# shield.net
KiCad netlist of a schematic drawn in EAGLE
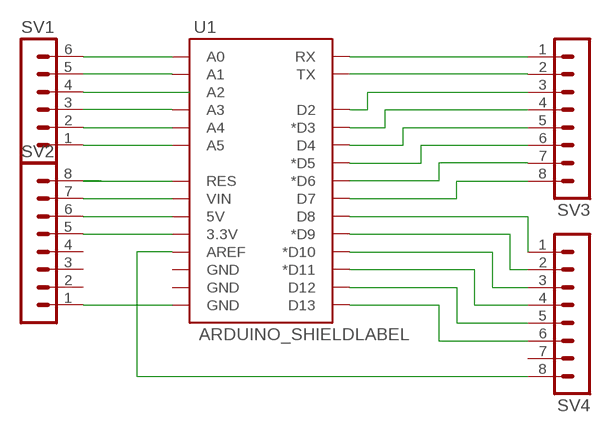
[diagram p0: schematic, sheet 1]

(export (version "E")
  (design (tool "Eeschema 10.0.6"))
  (components
    (comp (ref "SV1")
      (value "MA06-1")
      (footprint "eagle-import:MA06-1")
      (libsource (lib "eagle-import") (part "MA06-1"))
    )
    (comp (ref "SV2")
      (value "MA08-1")
      (footprint "eagle-import:MA08-1")
      (libsource (lib "eagle-import") (part "MA08-1"))
    )
    (comp (ref "SV3")
      (value "MA08-1")
      (footprint "eagle-import:MA08-1")
      (fields (field (name "OC_FARNELL") "unknown") (field (name "OC_NEWARK") "unknown"))
      (libsource (lib "eagle-import") (part "MA08-1"))
    )
    (comp (ref "SV4")
      (value "MA08-1")
      (footprint "eagle-import:MA08-1")
      (fields (field (name "OC_FARNELL") "unknown") (field (name "OC_NEWARK") "unknown"))
      (libsource (lib "eagle-import") (part "MA08-1"))
    )
    (comp (ref "U1")
      (value "ARDUINO_SHIELDLABEL")
      (footprint "eagle-import:DUEMILANOVE_SHIELD")
      (libsource (lib "eagle-import") (part "ARDUINO_SHIELDLABEL"))
    )
  )
  (nets
    (net (code "1") (name "Net-(SV1-Pad1)") (class "Default")
      (node (ref "SV1") (pin "1") (pinfunction "1_1") (pintype "passive"))
      (node (ref "U1") (pin "A5") (pinfunction "A5_A5") (pintype "bidirectional"))
    )
    (net (code "2") (name "Net-(SV1-Pad2)") (class "Default")
      (node (ref "SV1") (pin "2") (pinfunction "2_2") (pintype "passive"))
      (node (ref "U1") (pin "A4") (pinfunction "A4_A4") (pintype "bidirectional"))
    )
    (net (code "3") (name "Net-(SV1-Pad3)") (class "Default")
      (node (ref "SV1") (pin "3") (pinfunction "3_3") (pintype "passive"))
      (node (ref "U1") (pin "A3") (pinfunction "A3_A3") (pintype "bidirectional"))
    )
    (net (code "4") (name "Net-(SV1-Pad5)") (class "Default")
      (node (ref "SV1") (pin "5") (pinfunction "5_5") (pintype "passive"))
      (node (ref "U1") (pin "A1") (pinfunction "A1_A1") (pintype "bidirectional"))
    )
    (net (code "5") (name "Net-(SV1-Pad6)") (class "Default")
      (node (ref "SV1") (pin "6") (pinfunction "6_6") (pintype "passive"))
      (node (ref "U1") (pin "A0") (pinfunction "A0_A0") (pintype "bidirectional"))
    )
    (net (code "6") (name "Net-(SV2-Pad1)") (class "Default")
      (node (ref "SV2") (pin "1") (pinfunction "1_1") (pintype "passive"))
      (node (ref "U1") (pin "GND@0") (pinfunction "GND_GND@0") (pintype "bidirectional"))
    )
    (net (code "7") (name "Net-(SV2-Pad5)") (class "Default")
      (node (ref "SV2") (pin "5") (pinfunction "5_5") (pintype "passive"))
      (node (ref "U1") (pin "3.3V") (pinfunction "3.3V_3.3V") (pintype "bidirectional"))
    )
    (net (code "8") (name "Net-(SV2-Pad6)") (class "Default")
      (node (ref "SV2") (pin "6") (pinfunction "6_6") (pintype "passive"))
      (node (ref "U1") (pin "5V") (pinfunction "5V_5V") (pintype "bidirectional"))
    )
    (net (code "9") (name "Net-(SV2-Pad7)") (class "Default")
      (node (ref "SV2") (pin "7") (pinfunction "7_7") (pintype "passive"))
      (node (ref "U1") (pin "VIN") (pinfunction "VIN_VIN") (pintype "bidirectional"))
    )
    (net (code "10") (name "Net-(SV2-Pad8)") (class "Default")
      (node (ref "SV2") (pin "8") (pinfunction "8_8") (pintype "passive"))
      (node (ref "U1") (pin "RES") (pinfunction "RES_RES") (pintype "bidirectional"))
    )
    (net (code "11") (name "Net-(SV3-Pad1)") (class "Default")
      (node (ref "SV3") (pin "1") (pinfunction "1_1") (pintype "passive"))
      (node (ref "U1") (pin "RX") (pinfunction "RX_RX") (pintype "bidirectional"))
    )
    (net (code "12") (name "Net-(SV3-Pad2)") (class "Default")
      (node (ref "SV3") (pin "2") (pinfunction "2_2") (pintype "passive"))
      (node (ref "U1") (pin "TX") (pinfunction "TX_TX") (pintype "bidirectional"))
    )
    (net (code "13") (name "Net-(SV3-Pad3)") (class "Default")
      (node (ref "SV3") (pin "3") (pinfunction "3_3") (pintype "passive"))
      (node (ref "U1") (pin "D2") (pinfunction "D2_D2") (pintype "bidirectional"))
    )
    (net (code "14") (name "Net-(SV3-Pad5)") (class "Default")
      (node (ref "SV3") (pin "5") (pinfunction "5_5") (pintype "passive"))
      (node (ref "U1") (pin "D4") (pinfunction "D4_D4") (pintype "bidirectional"))
    )
    (net (code "15") (name "Net-(SV3-Pad8)") (class "Default")
      (node (ref "SV3") (pin "8") (pinfunction "8_8") (pintype "passive"))
      (node (ref "U1") (pin "D7") (pinfunction "D7_D7") (pintype "bidirectional"))
    )
    (net (code "16") (name "Net-(SV4-Pad1)") (class "Default")
      (node (ref "SV4") (pin "1") (pinfunction "1_1") (pintype "passive"))
      (node (ref "U1") (pin "D8") (pinfunction "D8_D8") (pintype "bidirectional"))
    )
    (net (code "17") (name "Net-(SV4-Pad5)") (class "Default")
      (node (ref "SV4") (pin "5") (pinfunction "5_5") (pintype "passive"))
      (node (ref "U1") (pin "D12") (pinfunction "D12_D12") (pintype "bidirectional"))
    )
    (net (code "18") (name "Net-(SV4-Pad6)") (class "Default")
      (node (ref "SV4") (pin "6") (pinfunction "6_6") (pintype "passive"))
      (node (ref "U1") (pin "D13") (pinfunction "D13_D13") (pintype "bidirectional"))
    )
    (net (code "19") (name "Net-(SV4-Pad8)") (class "Default")
      (node (ref "SV4") (pin "8") (pinfunction "8_8") (pintype "passive"))
      (node (ref "U1") (pin "AREF") (pinfunction "AREF_AREF") (pintype "bidirectional"))
    )
    (net (code "20") (name "Net-(U1-*D3)") (class "Default")
      (node (ref "SV3") (pin "4") (pinfunction "4_4") (pintype "passive"))
      (node (ref "U1") (pin "D3") (pinfunction "*D3_D3") (pintype "bidirectional"))
    )
    (net (code "21") (name "Net-(U1-*D5)") (class "Default")
      (node (ref "SV3") (pin "6") (pinfunction "6_6") (pintype "passive"))
      (node (ref "U1") (pin "D5") (pinfunction "*D5_D5") (pintype "bidirectional"))
    )
    (net (code "22") (name "Net-(U1-*D6)") (class "Default")
      (node (ref "SV3") (pin "7") (pinfunction "7_7") (pintype "passive"))
      (node (ref "U1") (pin "D6") (pinfunction "*D6_D6") (pintype "bidirectional"))
    )
    (net (code "23") (name "Net-(U1-*D9)") (class "Default")
      (node (ref "SV4") (pin "2") (pinfunction "2_2") (pintype "passive"))
      (node (ref "U1") (pin "D9") (pinfunction "*D9_D9") (pintype "bidirectional"))
    )
    (net (code "24") (name "Net-(U1-*D10)") (class "Default")
      (node (ref "SV4") (pin "3") (pinfunction "3_3") (pintype "passive"))
      (node (ref "U1") (pin "D10") (pinfunction "*D10_D10") (pintype "bidirectional"))
    )
    (net (code "25") (name "Net-(U1-*D11)") (class "Default")
      (node (ref "SV4") (pin "4") (pinfunction "4_4") (pintype "passive"))
      (node (ref "U1") (pin "D11") (pinfunction "*D11_D11") (pintype "bidirectional"))
    )
    (net (code "26") (name "unconnected-(SV1-Pad4)") (class "Default")
      (node (ref "SV1") (pin "4") (pinfunction "4_4") (pintype "passive"))
    )
    (net (code "27") (name "unconnected-(SV2-Pad2)") (class "Default")
      (node (ref "SV2") (pin "2") (pinfunction "2_2") (pintype "passive"))
    )
    (net (code "28") (name "unconnected-(SV2-Pad3)") (class "Default")
      (node (ref "SV2") (pin "3") (pinfunction "3_3") (pintype "passive"))
    )
    (net (code "29") (name "unconnected-(SV2-Pad4)") (class "Default")
      (node (ref "SV2") (pin "4") (pinfunction "4_4") (pintype "passive"))
    )
    (net (code "30") (name "unconnected-(SV4-Pad7)") (class "Default")
      (node (ref "SV4") (pin "7") (pinfunction "7_7") (pintype "passive"))
    )
    (net (code "31") (name "unconnected-(U1-GND-PadGND@1)") (class "Default")
      (node (ref "U1") (pin "GND@1") (pinfunction "GND_GND@1") (pintype "bidirectional"))
    )
    (net (code "32") (name "unconnected-(U1-GND-PadGND@2)") (class "Default")
      (node (ref "U1") (pin "GND@2") (pinfunction "GND_GND@2") (pintype "bidirectional"))
    )
    (net (code "33") (name "unconnected-(U1-PadA2)") (class "Default")
      (node (ref "U1") (pin "A2") (pinfunction "A2_A2") (pintype "bidirectional"))
    )
  )
)
